# 04_ALTIMETER.net
KiCad netlist of a schematic drawn in Altium Designer
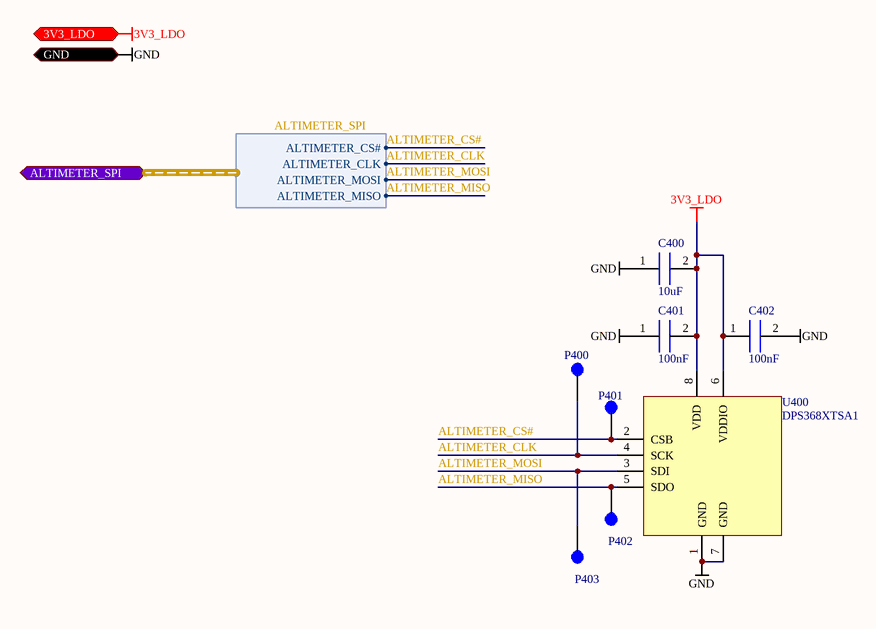
[diagram p0: 04_ALTIMETER.SchDoc]

(export (version "E")
  (design (tool "Eeschema 10.0.6"))
  (components
    (comp (ref "C400")
      (value "10uF")
      (footprint "CAP_0402")
      (description "CAPACITOR 10uF 20% 6.3V 0402 GRM155R60J106ME05D")
      (fields (field (name "TOLERANCE") "20%") (field (name "MANUFACTURER") "MURATA"))
      (libsource (lib "Capacitors") (part "10uF 20% 6.3V 0402 GRM155R60J106ME05D"))
    )
    (comp (ref "C401")
      (value "100nF")
      (footprint "CAP_0402")
      (description "CAPACITOR 100nF 10% X7R 0402")
      (fields (field (name "TOLERANCE") "10%") (field (name "MANUFACTURER") "MURATA"))
      (libsource (lib "Capacitors") (part "100nF_10%_16V_0402_GRM155R71C104KA88J"))
    )
    (comp (ref "C402")
      (value "100nF")
      (footprint "CAP_0402")
      (description "CAPACITOR 100nF 10% X7R 0402")
      (fields (field (name "TOLERANCE") "10%") (field (name "MANUFACTURER") "MURATA"))
      (libsource (lib "Capacitors") (part "100nF_10%_16V_0402_GRM155R71C104KA88J"))
    )
    (comp (ref "P400")
      (value "TEST_POINT_2mm")
      (footprint "TEST_POINT_2mm")
      (libsource (lib "Connectors") (part "TEST_POINT_2mm"))
    )
    (comp (ref "P401")
      (value "TEST_POINT_2mm")
      (footprint "TEST_POINT_2mm")
      (libsource (lib "Connectors") (part "TEST_POINT_2mm"))
    )
    (comp (ref "P402")
      (value "TEST_POINT_2mm")
      (footprint "TEST_POINT_2mm")
      (libsource (lib "Connectors") (part "TEST_POINT_2mm"))
    )
    (comp (ref "P403")
      (value "TEST_POINT_2mm")
      (footprint "TEST_POINT_2mm")
      (libsource (lib "Connectors") (part "TEST_POINT_2mm"))
    )
    (comp (ref "U400")
      (value "BAR_4V_0.002hPA_500nA_DPS368XTSA1")
      (footprint "DPS368XTSA1")
      (description "BAROMETRIC SENSOR 4V 0.002hPA 500nA DPS368XTSA1")
      (fields (field (name "MANUFACTURER") "INFINEON") (field (name "MANUFACTURER REFERENCE") "DPS368XTSA1"))
      (libsource (lib "Semiconductor") (part "BAR_4V_0.002hPA_500nA_DPS368XTSA1"))
    )
  )
  (nets
    (net (code "2") (name "/ALTIMETER_CLK") (class "Default")
      (node (ref "P400") (pin "1") (pinfunction "1_1") (pintype "passive"))
      (node (ref "U400") (pin "4") (pinfunction "SCK_4") (pintype "passive"))
    )
    (net (code "3") (name "/ALTIMETER_CS#") (class "Default")
      (node (ref "P401") (pin "1") (pinfunction "1_1") (pintype "passive"))
      (node (ref "U400") (pin "2") (pinfunction "CSB_2") (pintype "passive"))
    )
    (net (code "4") (name "/ALTIMETER_MISO") (class "Default")
      (node (ref "P402") (pin "1") (pinfunction "1_1") (pintype "passive"))
      (node (ref "U400") (pin "5") (pinfunction "SDO_5") (pintype "passive"))
    )
    (net (code "5") (name "/ALTIMETER_MOSI") (class "Default")
      (node (ref "P403") (pin "1") (pinfunction "1_1") (pintype "passive"))
      (node (ref "U400") (pin "3") (pinfunction "SDI_3") (pintype "passive"))
    )
    (net (code "7") (name "3V3_LDO") (class "Default")
      (node (ref "C400") (pin "2") (pinfunction "2_2") (pintype "passive"))
      (node (ref "C401") (pin "2") (pinfunction "2_2") (pintype "passive"))
      (node (ref "C402") (pin "1") (pinfunction "1_1") (pintype "passive"))
      (node (ref "U400") (pin "6") (pinfunction "VDDIO_6") (pintype "passive"))
      (node (ref "U400") (pin "8") (pinfunction "VDD_8") (pintype "passive"))
    )
    (net (code "8") (name "GND") (class "Default")
      (node (ref "C400") (pin "1") (pinfunction "1_1") (pintype "passive"))
      (node (ref "C401") (pin "1") (pinfunction "1_1") (pintype "passive"))
      (node (ref "C402") (pin "2") (pinfunction "2_2") (pintype "passive"))
      (node (ref "U400") (pin "1") (pinfunction "GND_1") (pintype "passive"))
      (node (ref "U400") (pin "7") (pinfunction "GND_7") (pintype "passive"))
    )
  )
)
